# Xtend-devboard.net
KiCad netlist of a schematic drawn in EAGLE
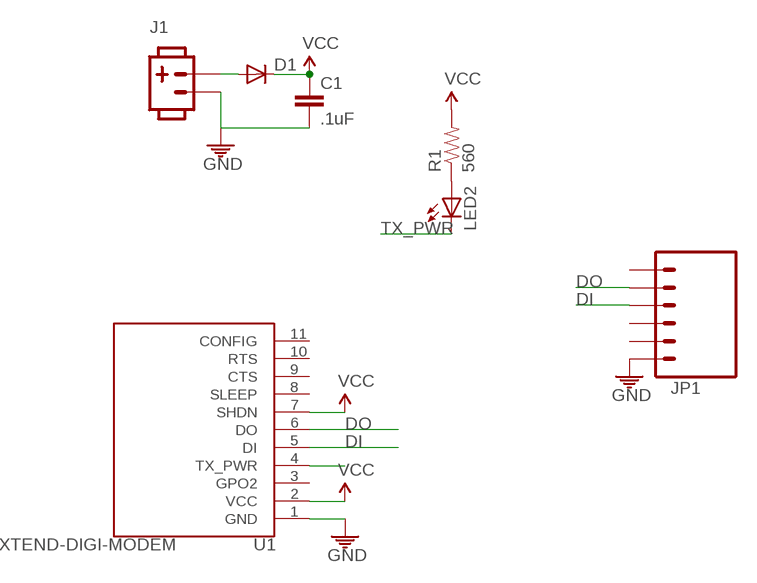
[diagram p0: schematic, sheet 1]

(export (version "E")
  (design (tool "Eeschema 10.0.6"))
  (components
    (comp (ref "C1")
      (value ".1uF")
      (footprint "eagle-import:CAP-PTH-5MM")
      (libsource (lib "eagle-import") (part "CAPPTH1"))
    )
    (comp (ref "D1")
      (value "DIODE1N4148")
      (footprint "eagle-import:DIODE-1N4148")
      (libsource (lib "eagle-import") (part "DIODE1N4148"))
    )
    (comp (ref "J1")
      (value "POW_CONNECTMALE")
      (footprint "eagle-import:SOCKET-MALE-3.96MM-2")
      (libsource (lib "eagle-import") (part "POW_CONNECTMALE"))
    )
    (comp (ref "JP1")
      (value "M06LOCK")
      (footprint "eagle-import:1X06_LOCK")
      (libsource (lib "eagle-import") (part "M06LOCK"))
    )
    (comp (ref "LED2")
      (value "LED5MM")
      (footprint "eagle-import:LED5MM")
      (libsource (lib "eagle-import") (part "LED5MM"))
    )
    (comp (ref "R1")
      (value "560")
      (footprint "eagle-import:AXIAL-0.3")
      (libsource (lib "eagle-import") (part "RESISTORAXIAL-0.3"))
    )
    (comp (ref "U1")
      (value "XTEND-DIGI-MODEM")
      (footprint "eagle-import:XTEND-DIGI-MODEM")
      (libsource (lib "eagle-import") (part "XTEND-DIGI-MODEM"))
    )
  )
  (nets
    (net (code "1") (name "/DI") (class "Default")
      (node (ref "JP1") (pin "4") (pinfunction "4_4") (pintype "passive"))
      (node (ref "U1") (pin "5") (pinfunction "DI_5") (pintype "bidirectional"))
    )
    (net (code "2") (name "/DO") (class "Default")
      (node (ref "JP1") (pin "5") (pinfunction "5_5") (pintype "passive"))
      (node (ref "U1") (pin "6") (pinfunction "DO_6") (pintype "bidirectional"))
    )
    (net (code "3") (name "/TX_PWR") (class "Default")
      (node (ref "LED2") (pin "K") (pinfunction "C_K") (pintype "passive"))
      (node (ref "U1") (pin "4") (pinfunction "TX_PWR_4") (pintype "bidirectional"))
    )
    (net (code "4") (name "GND") (class "Default")
      (node (ref "C1") (pin "2") (pinfunction "2_2") (pintype "passive"))
      (node (ref "J1") (pin "P$2") (pinfunction "2_P$2") (pintype "passive"))
      (node (ref "JP1") (pin "1") (pinfunction "1_1") (pintype "passive"))
      (node (ref "U1") (pin "1") (pinfunction "GND_1") (pintype "bidirectional"))
    )
    (net (code "5") (name "Net-(J1-1)") (class "Default")
      (node (ref "D1") (pin "A") (pinfunction "A_A") (pintype "passive"))
      (node (ref "J1") (pin "P$1") (pinfunction "1_P$1") (pintype "passive"))
    )
    (net (code "6") (name "Net-(R1-1)") (class "Default")
      (node (ref "LED2") (pin "A") (pinfunction "A_A") (pintype "passive"))
      (node (ref "R1") (pin "P$1") (pinfunction "1_P$1") (pintype "passive"))
    )
    (net (code "7") (name "VCC") (class "Default")
      (node (ref "C1") (pin "1") (pinfunction "1_1") (pintype "passive"))
      (node (ref "D1") (pin "C") (pinfunction "C_C") (pintype "passive"))
      (node (ref "R1") (pin "P$2") (pinfunction "2_P$2") (pintype "passive"))
      (node (ref "U1") (pin "2") (pinfunction "VCC_2") (pintype "bidirectional"))
      (node (ref "U1") (pin "7") (pinfunction "SHDN_7") (pintype "bidirectional"))
    )
    (net (code "8") (name "unconnected-(JP1-Pad2)") (class "Default")
      (node (ref "JP1") (pin "2") (pinfunction "2_2") (pintype "passive"))
    )
    (net (code "9") (name "unconnected-(JP1-Pad3)") (class "Default")
      (node (ref "JP1") (pin "3") (pinfunction "3_3") (pintype "passive"))
    )
    (net (code "10") (name "unconnected-(JP1-Pad6)") (class "Default")
      (node (ref "JP1") (pin "6") (pinfunction "6_6") (pintype "passive"))
    )
    (net (code "11") (name "unconnected-(U1-CONFIG-Pad11)") (class "Default")
      (node (ref "U1") (pin "11") (pinfunction "CONFIG_11") (pintype "bidirectional"))
    )
    (net (code "12") (name "unconnected-(U1-CTS-Pad9)") (class "Default")
      (node (ref "U1") (pin "9") (pinfunction "CTS_9") (pintype "bidirectional"))
    )
    (net (code "13") (name "unconnected-(U1-GPO2-Pad3)") (class "Default")
      (node (ref "U1") (pin "3") (pinfunction "GPO2_3") (pintype "bidirectional"))
    )
    (net (code "14") (name "unconnected-(U1-RTS-Pad10)") (class "Default")
      (node (ref "U1") (pin "10") (pinfunction "RTS_10") (pintype "bidirectional"))
    )
    (net (code "15") (name "unconnected-(U1-SLEEP-Pad8)") (class "Default")
      (node (ref "U1") (pin "8") (pinfunction "SLEEP_8") (pintype "bidirectional"))
    )
  )
)
